# sch.net
KiCad netlist of a schematic drawn in EAGLE
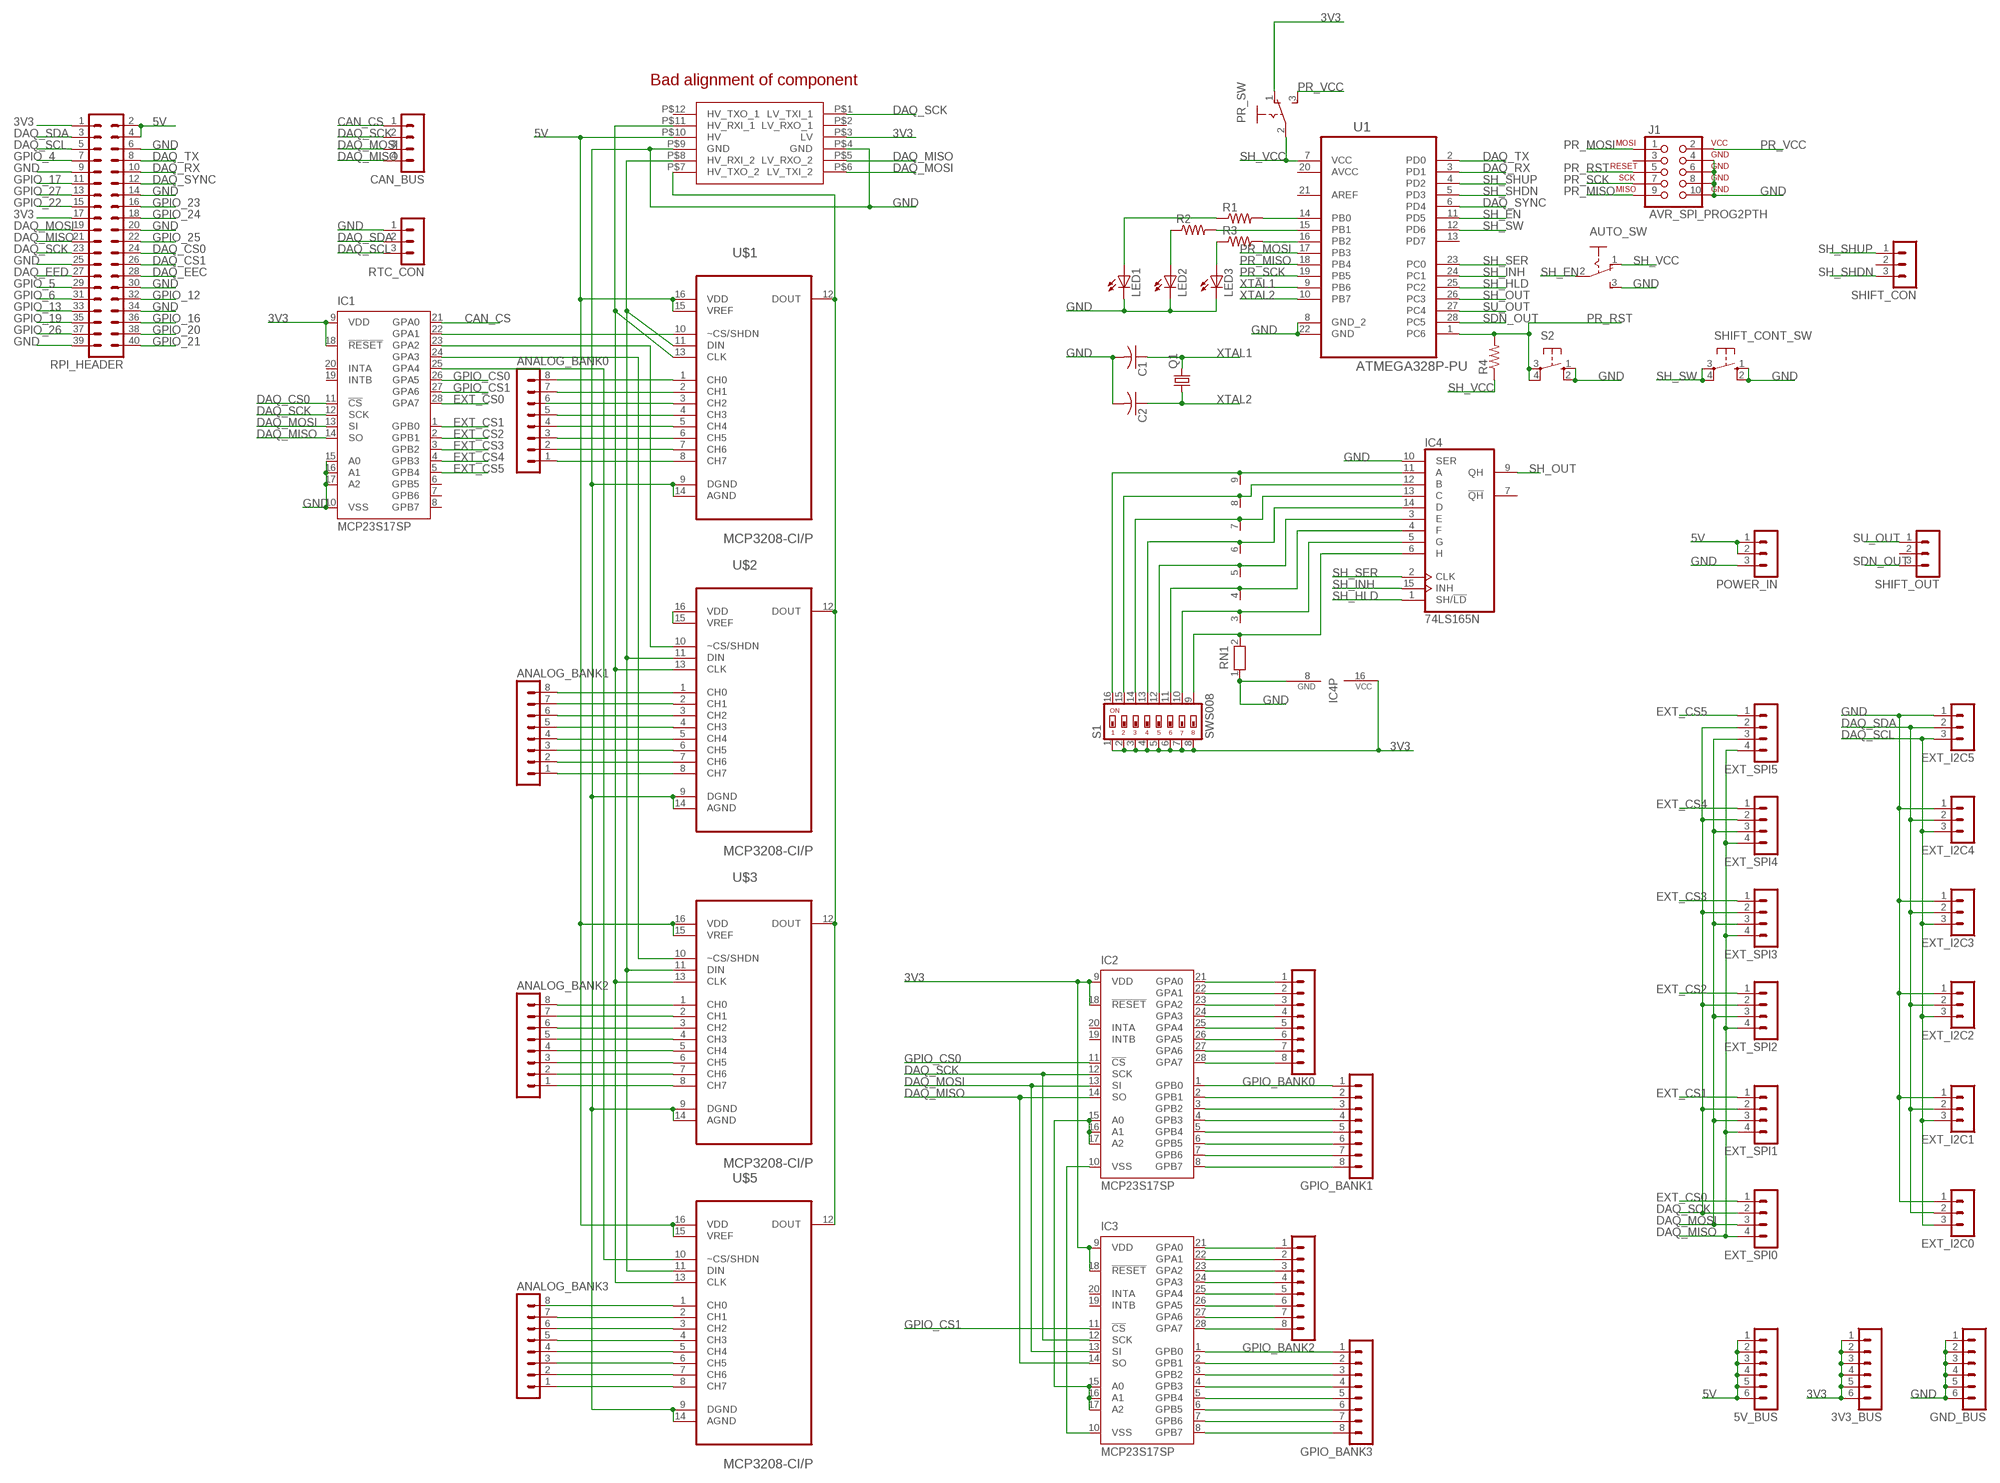
[diagram p0: schematic, sheet 1]

(export (version "E")
  (design (tool "Eeschema 10.0.6"))
  (components
    (comp (ref "3V3_BUS")
      (value "MA06-1")
      (footprint "eagle-import:MA06-1")
      (libsource (lib "eagle-import") (part "MA06-1"))
    )
    (comp (ref "5V_BUS")
      (value "MA06-1")
      (footprint "eagle-import:MA06-1")
      (libsource (lib "eagle-import") (part "MA06-1"))
    )
    (comp (ref "ANALOG_BANK0")
      (value "MA08-1")
      (footprint "eagle-import:MA08-1")
      (libsource (lib "eagle-import") (part "MA08-1"))
    )
    (comp (ref "ANALOG_BANK1")
      (value "MA08-1")
      (footprint "eagle-import:MA08-1")
      (libsource (lib "eagle-import") (part "MA08-1"))
    )
    (comp (ref "ANALOG_BANK2")
      (value "MA08-1")
      (footprint "eagle-import:MA08-1")
      (libsource (lib "eagle-import") (part "MA08-1"))
    )
    (comp (ref "ANALOG_BANK3")
      (value "MA08-1")
      (footprint "eagle-import:MA08-1")
      (libsource (lib "eagle-import") (part "MA08-1"))
    )
    (comp (ref "AUTO_SW")
      (value "255SB")
      (footprint "eagle-import:255SB")
      (libsource (lib "eagle-import") (part "255SB"))
    )
    (comp (ref "C1")
      (value "C-US025-025X050")
      (footprint "eagle-import:C025-025X050")
      (libsource (lib "eagle-import") (part "C-US025-025X050"))
    )
    (comp (ref "C2")
      (value "C-US025-025X050")
      (footprint "eagle-import:C025-025X050")
      (libsource (lib "eagle-import") (part "C-US025-025X050"))
    )
    (comp (ref "CAN_BUS")
      (value "MA04-1")
      (footprint "eagle-import:MA04-1")
      (libsource (lib "eagle-import") (part "MA04-1"))
    )
    (comp (ref "EXT_I2C0")
      (value "MA03-1")
      (footprint "eagle-import:MA03-1")
      (libsource (lib "eagle-import") (part "MA03-1"))
    )
    (comp (ref "EXT_I2C1")
      (value "MA03-1")
      (footprint "eagle-import:MA03-1")
      (libsource (lib "eagle-import") (part "MA03-1"))
    )
    (comp (ref "EXT_I2C2")
      (value "MA03-1")
      (footprint "eagle-import:MA03-1")
      (libsource (lib "eagle-import") (part "MA03-1"))
    )
    (comp (ref "EXT_I2C3")
      (value "MA03-1")
      (footprint "eagle-import:MA03-1")
      (libsource (lib "eagle-import") (part "MA03-1"))
    )
    (comp (ref "EXT_I2C4")
      (value "MA03-1")
      (footprint "eagle-import:MA03-1")
      (libsource (lib "eagle-import") (part "MA03-1"))
    )
    (comp (ref "EXT_I2C5")
      (value "MA03-1")
      (footprint "eagle-import:MA03-1")
      (libsource (lib "eagle-import") (part "MA03-1"))
    )
    (comp (ref "EXT_SPI0")
      (value "MA04-1")
      (footprint "eagle-import:MA04-1")
      (libsource (lib "eagle-import") (part "MA04-1"))
    )
    (comp (ref "EXT_SPI1")
      (value "MA04-1")
      (footprint "eagle-import:MA04-1")
      (libsource (lib "eagle-import") (part "MA04-1"))
    )
    (comp (ref "EXT_SPI2")
      (value "MA04-1")
      (footprint "eagle-import:MA04-1")
      (libsource (lib "eagle-import") (part "MA04-1"))
    )
    (comp (ref "EXT_SPI3")
      (value "MA04-1")
      (footprint "eagle-import:MA04-1")
      (libsource (lib "eagle-import") (part "MA04-1"))
    )
    (comp (ref "EXT_SPI4")
      (value "MA04-1")
      (footprint "eagle-import:MA04-1")
      (libsource (lib "eagle-import") (part "MA04-1"))
    )
    (comp (ref "EXT_SPI5")
      (value "MA04-1")
      (footprint "eagle-import:MA04-1")
      (libsource (lib "eagle-import") (part "MA04-1"))
    )
    (comp (ref "GND_BUS")
      (value "MA06-1")
      (footprint "eagle-import:MA06-1")
      (libsource (lib "eagle-import") (part "MA06-1"))
    )
    (comp (ref "GPIO_BANK0")
      (value "MA08-1")
      (footprint "eagle-import:MA08-1")
      (libsource (lib "eagle-import") (part "MA08-1"))
    )
    (comp (ref "GPIO_BANK1")
      (value "MA08-1")
      (footprint "eagle-import:MA08-1")
      (libsource (lib "eagle-import") (part "MA08-1"))
    )
    (comp (ref "GPIO_BANK2")
      (value "MA08-1")
      (footprint "eagle-import:MA08-1")
      (libsource (lib "eagle-import") (part "MA08-1"))
    )
    (comp (ref "GPIO_BANK3")
      (value "MA08-1")
      (footprint "eagle-import:MA08-1")
      (libsource (lib "eagle-import") (part "MA08-1"))
    )
    (comp (ref "IC1")
      (value "MCP23S17SP")
      (footprint "eagle-import:DIL28-3")
      (fields (field (name "MF") "MICROCHIP") (field (name "MPN") "MCP23S17-E/SP"))
      (libsource (lib "eagle-import") (part "MCP23S17SP"))
    )
    (comp (ref "IC2")
      (value "MCP23S17SP")
      (footprint "eagle-import:DIL28-3")
      (fields (field (name "MF") "MICROCHIP") (field (name "MPN") "MCP23S17-E/SP"))
      (libsource (lib "eagle-import") (part "MCP23S17SP"))
    )
    (comp (ref "IC3")
      (value "MCP23S17SP")
      (footprint "eagle-import:DIL28-3")
      (fields (field (name "MF") "MICROCHIP") (field (name "MPN") "MCP23S17-E/SP"))
      (libsource (lib "eagle-import") (part "MCP23S17SP"))
    )
    (comp (ref "IC4")
      (value "74LS165N")
      (footprint "eagle-import:DIL16")
      (libsource (lib "eagle-import") (part "74165NLS"))
    )
    (comp (ref "J1")
      (value "AVR_SPI_PROG2PTH")
      (footprint "eagle-import:AVR_ICSP")
      (libsource (lib "eagle-import") (part "AVR_SPI_PROG2PTH"))
    )
    (comp (ref "LED1")
      (value "LED3MM")
      (footprint "eagle-import:LED3MM")
      (libsource (lib "eagle-import") (part "LED3MM"))
    )
    (comp (ref "LED2")
      (value "LED3MM")
      (footprint "eagle-import:LED3MM")
      (libsource (lib "eagle-import") (part "LED3MM"))
    )
    (comp (ref "LED3")
      (value "LED3MM")
      (footprint "eagle-import:LED3MM")
      (libsource (lib "eagle-import") (part "LED3MM"))
    )
    (comp (ref "POWER_IN")
      (value "MA03-1")
      (footprint "eagle-import:MA03-1")
      (libsource (lib "eagle-import") (part "MA03-1"))
    )
    (comp (ref "PR_SW")
      (value "255SB")
      (footprint "eagle-import:255SB")
      (libsource (lib "eagle-import") (part "255SB"))
    )
    (comp (ref "Q1")
      (value "CRYSTALHC49S")
      (footprint "eagle-import:HC49_S")
      (libsource (lib "eagle-import") (part "CRYSTALHC49S"))
    )
    (comp (ref "R1")
      (value "R-US_0204/5")
      (footprint "eagle-import:0204_5")
      (libsource (lib "eagle-import") (part "R-US_0204/5"))
    )
    (comp (ref "R2")
      (value "R-US_0204/5")
      (footprint "eagle-import:0204_5")
      (libsource (lib "eagle-import") (part "R-US_0204/5"))
    )
    (comp (ref "R3")
      (value "R-US_0204/5")
      (footprint "eagle-import:0204_5")
      (libsource (lib "eagle-import") (part "R-US_0204/5"))
    )
    (comp (ref "R4")
      (value "R-US_0204/5")
      (footprint "eagle-import:0204_5")
      (libsource (lib "eagle-import") (part "R-US_0204/5"))
    )
    (comp (ref "RN1")
      (value "RN08")
      (footprint "eagle-import:RN-9")
      (libsource (lib "eagle-import") (part "RN08"))
    )
    (comp (ref "RPI_HEADER")
      (value "MA20-2")
      (footprint "eagle-import:MA20-2")
      (libsource (lib "eagle-import") (part "MA20-2"))
    )
    (comp (ref "RTC_CON")
      (value "MA03-1")
      (footprint "eagle-import:MA03-1")
      (libsource (lib "eagle-import") (part "MA03-1"))
    )
    (comp (ref "S1")
      (value "SWS008")
      (footprint "eagle-import:SMS-008")
      (libsource (lib "eagle-import") (part "SWS008"))
    )
    (comp (ref "S2")
      (value "10-XX")
      (footprint "eagle-import:B3F-10XX")
      (fields (field (name "MPN") "B3F-1000"))
      (libsource (lib "eagle-import") (part "10-XX"))
    )
    (comp (ref "SHIFT_CON")
      (value "MA03-1")
      (footprint "eagle-import:MA03-1")
      (libsource (lib "eagle-import") (part "MA03-1"))
    )
    (comp (ref "SHIFT_CONT_SW")
      (value "10-XX")
      (footprint "eagle-import:B3F-10XX")
      (fields (field (name "MPN") "B3F-1000"))
      (libsource (lib "eagle-import") (part "10-XX"))
    )
    (comp (ref "SHIFT_OUT")
      (value "MA03-1")
      (footprint "eagle-import:MA03-1")
      (libsource (lib "eagle-import") (part "MA03-1"))
    )
    (comp (ref "U$1")
      (value "MCP3208-CI/P")
      (footprint "eagle-import:DIP254P762X432-16")
      (libsource (lib "eagle-import") (part "MCP3208-CI/P"))
    )
    (comp (ref "U$2")
      (value "MCP3208-CI/P")
      (footprint "eagle-import:DIP254P762X432-16")
      (libsource (lib "eagle-import") (part "MCP3208-CI/P"))
    )
    (comp (ref "U$3")
      (value "MCP3208-CI/P")
      (footprint "eagle-import:DIP254P762X432-16")
      (libsource (lib "eagle-import") (part "MCP3208-CI/P"))
    )
    (comp (ref "U$4")
      (value "LOGIC_LEVEL_CONVERTER")
      (footprint "eagle-import:LOGIC_LEVEL_CONVERTER")
      (libsource (lib "eagle-import") (part "LOGIC_LEVEL_CONVERTER"))
    )
    (comp (ref "U$5")
      (value "MCP3208-CI/P")
      (footprint "eagle-import:DIP254P762X432-16")
      (libsource (lib "eagle-import") (part "MCP3208-CI/P"))
    )
    (comp (ref "U1")
      (value "ATMEGA328P-PU")
      (footprint "eagle-import:DIP254P762X457-28")
      (libsource (lib "eagle-import") (part "ATMEGA328P-PU"))
    )
  )
  (nets
    (net (code "1") (name "/3V3") (class "Default")
      (node (ref "3V3_BUS") (pin "1") (pinfunction "1_1") (pintype "passive"))
      (node (ref "3V3_BUS") (pin "2") (pinfunction "2_2") (pintype "passive"))
      (node (ref "3V3_BUS") (pin "3") (pinfunction "3_3") (pintype "passive"))
      (node (ref "3V3_BUS") (pin "4") (pinfunction "4_4") (pintype "passive"))
      (node (ref "3V3_BUS") (pin "5") (pinfunction "5_5") (pintype "passive"))
      (node (ref "3V3_BUS") (pin "6") (pinfunction "6_6") (pintype "passive"))
      (node (ref "IC1") (pin "18") (pinfunction "~{RESET}_18") (pintype "input"))
      (node (ref "IC1") (pin "9") (pinfunction "VDD_9") (pintype "power_in"))
      (node (ref "IC2") (pin "18") (pinfunction "~{RESET}_18") (pintype "input"))
      (node (ref "IC2") (pin "9") (pinfunction "VDD_9") (pintype "power_in"))
      (node (ref "IC3") (pin "18") (pinfunction "~{RESET}_18") (pintype "input"))
      (node (ref "IC3") (pin "9") (pinfunction "VDD_9") (pintype "power_in"))
      (node (ref "IC4") (pin "16") (pinfunction "VCC_16") (pintype "power_in"))
      (node (ref "PR_SW") (pin "1") (pinfunction "O_1") (pintype "passive"))
      (node (ref "RPI_HEADER") (pin "1") (pinfunction "1_1") (pintype "passive"))
      (node (ref "RPI_HEADER") (pin "17") (pinfunction "17_17") (pintype "passive"))
      (node (ref "S1") (pin "1") (pinfunction "1_1") (pintype "passive"))
      (node (ref "S1") (pin "2") (pinfunction "2_2") (pintype "passive"))
      (node (ref "S1") (pin "3") (pinfunction "3_3") (pintype "passive"))
      (node (ref "S1") (pin "4") (pinfunction "4_4") (pintype "passive"))
      (node (ref "S1") (pin "5") (pinfunction "5_5") (pintype "passive"))
      (node (ref "S1") (pin "6") (pinfunction "6_6") (pintype "passive"))
      (node (ref "S1") (pin "7") (pinfunction "7_7") (pintype "passive"))
      (node (ref "S1") (pin "8") (pinfunction "8_8") (pintype "passive"))
      (node (ref "U$4") (pin "P$3") (pinfunction "LV_P$3") (pintype "bidirectional"))
    )
    (net (code "2") (name "/5V") (class "Default")
      (node (ref "5V_BUS") (pin "1") (pinfunction "1_1") (pintype "passive"))
      (node (ref "5V_BUS") (pin "2") (pinfunction "2_2") (pintype "passive"))
      (node (ref "5V_BUS") (pin "3") (pinfunction "3_3") (pintype "passive"))
      (node (ref "5V_BUS") (pin "4") (pinfunction "4_4") (pintype "passive"))
      (node (ref "5V_BUS") (pin "5") (pinfunction "5_5") (pintype "passive"))
      (node (ref "5V_BUS") (pin "6") (pinfunction "6_6") (pintype "passive"))
      (node (ref "POWER_IN") (pin "1") (pinfunction "1_1") (pintype "passive"))
      (node (ref "POWER_IN") (pin "2") (pinfunction "2_2") (pintype "passive"))
      (node (ref "RPI_HEADER") (pin "2") (pinfunction "2_2") (pintype "passive"))
      (node (ref "RPI_HEADER") (pin "4") (pinfunction "4_4") (pintype "passive"))
      (node (ref "U$1") (pin "15") (pinfunction "VREF_15") (pintype "power_in"))
      (node (ref "U$1") (pin "16") (pinfunction "VDD_16") (pintype "power_in"))
      (node (ref "U$3") (pin "15") (pinfunction "VREF_15") (pintype "power_in"))
      (node (ref "U$3") (pin "16") (pinfunction "VDD_16") (pintype "power_in"))
      (node (ref "U$4") (pin "P$10") (pinfunction "HV_P$10") (pintype "bidirectional"))
      (node (ref "U$5") (pin "15") (pinfunction "VREF_15") (pintype "power_in"))
      (node (ref "U$5") (pin "16") (pinfunction "VDD_16") (pintype "power_in"))
    )
    (net (code "3") (name "/AVCC") (class "Default")
      (node (ref "U1") (pin "20") (pinfunction "AVCC_20") (pintype "power_in"))
    )
    (net (code "4") (name "/CAN_CS") (class "Default")
      (node (ref "CAN_BUS") (pin "1") (pinfunction "1_1") (pintype "passive"))
      (node (ref "IC1") (pin "21") (pinfunction "GPA0_21") (pintype "bidirectional"))
    )
    (net (code "5") (name "/DAQ_CS0") (class "Default")
      (node (ref "IC1") (pin "11") (pinfunction "~{CS}_11") (pintype "input"))
      (node (ref "RPI_HEADER") (pin "24") (pinfunction "24_24") (pintype "passive"))
    )
    (net (code "6") (name "/DAQ_CS1") (class "Default")
      (node (ref "RPI_HEADER") (pin "26") (pinfunction "26_26") (pintype "passive"))
    )
    (net (code "7") (name "/DAQ_EEC") (class "Default")
      (node (ref "RPI_HEADER") (pin "28") (pinfunction "28_28") (pintype "passive"))
    )
    (net (code "8") (name "/DAQ_EED") (class "Default")
      (node (ref "RPI_HEADER") (pin "27") (pinfunction "27_27") (pintype "passive"))
    )
    (net (code "9") (name "/DAQ_MISO") (class "Default")
      (node (ref "CAN_BUS") (pin "4") (pinfunction "4_4") (pintype "passive"))
      (node (ref "EXT_SPI0") (pin "4") (pinfunction "4_4") (pintype "passive"))
      (node (ref "EXT_SPI1") (pin "4") (pinfunction "4_4") (pintype "passive"))
      (node (ref "EXT_SPI2") (pin "4") (pinfunction "4_4") (pintype "passive"))
      (node (ref "EXT_SPI3") (pin "4") (pinfunction "4_4") (pintype "passive"))
      (node (ref "EXT_SPI4") (pin "4") (pinfunction "4_4") (pintype "passive"))
      (node (ref "EXT_SPI5") (pin "4") (pinfunction "4_4") (pintype "passive"))
      (node (ref "IC1") (pin "14") (pinfunction "SO_14") (pintype "output"))
      (node (ref "IC2") (pin "14") (pinfunction "SO_14") (pintype "output"))
      (node (ref "IC3") (pin "14") (pinfunction "SO_14") (pintype "output"))
      (node (ref "RPI_HEADER") (pin "21") (pinfunction "21_21") (pintype "passive"))
      (node (ref "U$4") (pin "P$5") (pinfunction "LV_RXO_2_P$5") (pintype "bidirectional"))
    )
    (net (code "10") (name "/DAQ_MOSI") (class "Default")
      (node (ref "CAN_BUS") (pin "3") (pinfunction "3_3") (pintype "passive"))
      (node (ref "EXT_SPI0") (pin "3") (pinfunction "3_3") (pintype "passive"))
      (node (ref "EXT_SPI1") (pin "3") (pinfunction "3_3") (pintype "passive"))
      (node (ref "EXT_SPI2") (pin "3") (pinfunction "3_3") (pintype "passive"))
      (node (ref "EXT_SPI3") (pin "3") (pinfunction "3_3") (pintype "passive"))
      (node (ref "EXT_SPI4") (pin "3") (pinfunction "3_3") (pintype "passive"))
      (node (ref "EXT_SPI5") (pin "3") (pinfunction "3_3") (pintype "passive"))
      (node (ref "IC1") (pin "13") (pinfunction "SI_13") (pintype "input"))
      (node (ref "IC2") (pin "13") (pinfunction "SI_13") (pintype "input"))
      (node (ref "IC3") (pin "13") (pinfunction "SI_13") (pintype "input"))
      (node (ref "RPI_HEADER") (pin "19") (pinfunction "19_19") (pintype "passive"))
      (node (ref "U$4") (pin "P$6") (pinfunction "LV_TXI_2_P$6") (pintype "bidirectional"))
    )
    (net (code "11") (name "/DAQ_RX") (class "Default")
      (node (ref "RPI_HEADER") (pin "10") (pinfunction "10_10") (pintype "passive"))
      (node (ref "U1") (pin "3") (pinfunction "PD1_3") (pintype "bidirectional"))
    )
    (net (code "12") (name "/DAQ_SCK") (class "Default")
      (node (ref "CAN_BUS") (pin "2") (pinfunction "2_2") (pintype "passive"))
      (node (ref "EXT_SPI0") (pin "2") (pinfunction "2_2") (pintype "passive"))
      (node (ref "EXT_SPI1") (pin "2") (pinfunction "2_2") (pintype "passive"))
      (node (ref "EXT_SPI2") (pin "2") (pinfunction "2_2") (pintype "passive"))
      (node (ref "EXT_SPI3") (pin "2") (pinfunction "2_2") (pintype "passive"))
      (node (ref "EXT_SPI4") (pin "2") (pinfunction "2_2") (pintype "passive"))
      (node (ref "EXT_SPI5") (pin "2") (pinfunction "2_2") (pintype "passive"))
      (node (ref "IC1") (pin "12") (pinfunction "SCK_12") (pintype "input"))
      (node (ref "IC2") (pin "12") (pinfunction "SCK_12") (pintype "input"))
      (node (ref "IC3") (pin "12") (pinfunction "SCK_12") (pintype "input"))
      (node (ref "RPI_HEADER") (pin "23") (pinfunction "23_23") (pintype "passive"))
      (node (ref "U$4") (pin "P$1") (pinfunction "LV_TXI_1_P$1") (pintype "bidirectional"))
    )
    (net (code "13") (name "/DAQ_SCL") (class "Default")
      (node (ref "EXT_I2C0") (pin "3") (pinfunction "3_3") (pintype "passive"))
      (node (ref "EXT_I2C1") (pin "3") (pinfunction "3_3") (pintype "passive"))
      (node (ref "EXT_I2C2") (pin "3") (pinfunction "3_3") (pintype "passive"))
      (node (ref "EXT_I2C3") (pin "3") (pinfunction "3_3") (pintype "passive"))
      (node (ref "EXT_I2C4") (pin "3") (pinfunction "3_3") (pintype "passive"))
      (node (ref "EXT_I2C5") (pin "3") (pinfunction "3_3") (pintype "passive"))
      (node (ref "RPI_HEADER") (pin "5") (pinfunction "5_5") (pintype "passive"))
      (node (ref "RTC_CON") (pin "3") (pinfunction "3_3") (pintype "passive"))
    )
    (net (code "14") (name "/DAQ_SDA") (class "Default")
      (node (ref "EXT_I2C0") (pin "2") (pinfunction "2_2") (pintype "passive"))
      (node (ref "EXT_I2C1") (pin "2") (pinfunction "2_2") (pintype "passive"))
      (node (ref "EXT_I2C2") (pin "2") (pinfunction "2_2") (pintype "passive"))
      (node (ref "EXT_I2C3") (pin "2") (pinfunction "2_2") (pintype "passive"))
      (node (ref "EXT_I2C4") (pin "2") (pinfunction "2_2") (pintype "passive"))
      (node (ref "EXT_I2C5") (pin "2") (pinfunction "2_2") (pintype "passive"))
      (node (ref "RPI_HEADER") (pin "3") (pinfunction "3_3") (pintype "passive"))
      (node (ref "RTC_CON") (pin "2") (pinfunction "2_2") (pintype "passive"))
    )
    (net (code "15") (name "/DAQ_SYNC") (class "Default")
      (node (ref "RPI_HEADER") (pin "12") (pinfunction "12_12") (pintype "passive"))
      (node (ref "U1") (pin "6") (pinfunction "PD4_6") (pintype "bidirectional"))
    )
    (net (code "16") (name "/DAQ_TX") (class "Default")
      (node (ref "RPI_HEADER") (pin "8") (pinfunction "8_8") (pintype "passive"))
      (node (ref "U1") (pin "2") (pinfunction "PD0_2") (pintype "bidirectional"))
    )
    (net (code "17") (name "/EXT_CS0") (class "Default")
      (node (ref "EXT_SPI0") (pin "1") (pinfunction "1_1") (pintype "passive"))
      (node (ref "IC1") (pin "28") (pinfunction "GPA7_28") (pintype "bidirectional"))
    )
    (net (code "18") (name "/EXT_CS1") (class "Default")
      (node (ref "EXT_SPI1") (pin "1") (pinfunction "1_1") (pintype "passive"))
      (node (ref "IC1") (pin "1") (pinfunction "GPB0_1") (pintype "bidirectional"))
    )
    (net (code "19") (name "/EXT_CS2") (class "Default")
      (node (ref "EXT_SPI2") (pin "1") (pinfunction "1_1") (pintype "passive"))
      (node (ref "IC1") (pin "2") (pinfunction "GPB1_2") (pintype "bidirectional"))
    )
    (net (code "20") (name "/EXT_CS3") (class "Default")
      (node (ref "EXT_SPI3") (pin "1") (pinfunction "1_1") (pintype "passive"))
      (node (ref "IC1") (pin "3") (pinfunction "GPB2_3") (pintype "bidirectional"))
    )
    (net (code "21") (name "/EXT_CS4") (class "Default")
      (node (ref "EXT_SPI4") (pin "1") (pinfunction "1_1") (pintype "passive"))
      (node (ref "IC1") (pin "4") (pinfunction "GPB3_4") (pintype "bidirectional"))
    )
    (net (code "22") (name "/EXT_CS5") (class "Default")
      (node (ref "EXT_SPI5") (pin "1") (pinfunction "1_1") (pintype "passive"))
      (node (ref "IC1") (pin "5") (pinfunction "GPB4_5") (pintype "bidirectional"))
    )
    (net (code "23") (name "/GND") (class "Default")
      (node (ref "AUTO_SW") (pin "3") (pinfunction "S_3") (pintype "passive"))
      (node (ref "C1") (pin "2") (pinfunction "2_2") (pintype "passive"))
      (node (ref "C2") (pin "2") (pinfunction "2_2") (pintype "passive"))
      (node (ref "EXT_I2C0") (pin "1") (pinfunction "1_1") (pintype "passive"))
      (node (ref "EXT_I2C1") (pin "1") (pinfunction "1_1") (pintype "passive"))
      (node (ref "EXT_I2C2") (pin "1") (pinfunction "1_1") (pintype "passive"))
      (node (ref "EXT_I2C3") (pin "1") (pinfunction "1_1") (pintype "passive"))
      (node (ref "EXT_I2C4") (pin "1") (pinfunction "1_1") (pintype "passive"))
      (node (ref "EXT_I2C5") (pin "1") (pinfunction "1_1") (pintype "passive"))
      (node (ref "GND_BUS") (pin "1") (pinfunction "1_1") (pintype "passive"))
      (node (ref "GND_BUS") (pin "2") (pinfunction "2_2") (pintype "passive"))
      (node (ref "GND_BUS") (pin "3") (pinfunction "3_3") (pintype "passive"))
      (node (ref "GND_BUS") (pin "4") (pinfunction "4_4") (pintype "passive"))
      (node (ref "GND_BUS") (pin "5") (pinfunction "5_5") (pintype "passive"))
      (node (ref "GND_BUS") (pin "6") (pinfunction "6_6") (pintype "passive"))
      (node (ref "IC1") (pin "10") (pinfunction "VSS_10") (pintype "power_in"))
      (node (ref "IC1") (pin "15") (pinfunction "A0_15") (pintype "input"))
      (node (ref "IC1") (pin "16") (pinfunction "A1_16") (pintype "input"))
      (node (ref "IC1") (pin "17") (pinfunction "A2_17") (pintype "input"))
      (node (ref "IC4") (pin "10") (pinfunction "SER_10") (pintype "input"))
      (node (ref "IC4") (pin "8") (pinfunction "GND_8") (pintype "power_in"))
      (node (ref "J1") (pin "10") (pinfunction "GND_10") (pintype "power_in"))
      (node (ref "J1") (pin "4") (pinfunction "GND_4") (pintype "power_in"))
      (node (ref "J1") (pin "6") (pinfunction "GND_6") (pintype "power_in"))
      (node (ref "J1") (pin "8") (pinfunction "GND_8") (pintype "power_in"))
      (node (ref "LED1") (pin "K") (pinfunction "C_K") (pintype "passive"))
      (node (ref "LED2") (pin "K") (pinfunction "C_K") (pintype "passive"))
      (node (ref "LED3") (pin "K") (pinfunction "C_K") (pintype "passive"))
      (node (ref "POWER_IN") (pin "3") (pinfunction "3_3") (pintype "passive"))
      (node (ref "RN1") (pin "1") (pinfunction "1_1") (pintype "passive"))
      (node (ref "RPI_HEADER") (pin "14") (pinfunction "14_14") (pintype "passive"))
      (node (ref "RPI_HEADER") (pin "20") (pinfunction "20_20") (pintype "passive"))
      (node (ref "RPI_HEADER") (pin "25") (pinfunction "25_25") (pintype "passive"))
      (node (ref "RPI_HEADER") (pin "30") (pinfunction "30_30") (pintype "passive"))
      (node (ref "RPI_HEADER") (pin "34") (pinfunction "34_34") (pintype "passive"))
      (node (ref "RPI_HEADER") (pin "39") (pinfunction "39_39") (pintype "passive"))
      (node (ref "RPI_HEADER") (pin "6") (pinfunction "6_6") (pintype "passive"))
      (node (ref "RPI_HEADER") (pin "9") (pinfunction "9_9") (pintype "passive"))
      (node (ref "RTC_CON") (pin "1") (pinfunction "1_1") (pintype "passive"))
      (node (ref "S2") (pin "1") (pinfunction "S_1") (pintype "passive"))
      (node (ref "S2") (pin "2") (pinfunction "S1_2") (pintype "passive"))
      (node (ref "SHIFT_CONT_SW") (pin "1") (pinfunction "S_1") (pintype "passive"))
      (node (ref "SHIFT_CONT_SW") (pin "2") (pinfunction "S1_2") (pintype "passive"))
      (node (ref "U$1") (pin "14") (pinfunction "AGND_14") (pintype "passive"))
      (node (ref "U$1") (pin "9") (pinfunction "DGND_9") (pintype "passive"))
      (node (ref "U$2") (pin "14") (pinfunction "AGND_14") (pintype "passive"))
      (node (ref "U$2") (pin "9") (pinfunction "DGND_9") (pintype "passive"))
      (node (ref "U$3") (pin "14") (pinfunction "AGND_14") (pintype "passive"))
      (node (ref "U$3") (pin "9") (pinfunction "DGND_9") (pintype "passive"))
      (node (ref "U$4") (pin "P$4") (pinfunction "GND_P$4") (pintype "bidirectional"))
      (node (ref "U$4") (pin "P$9") (pinfunction "GND_P$9") (pintype "bidirectional"))
      (node (ref "U$5") (pin "14") (pinfunction "AGND_14") (pintype "passive"))
      (node (ref "U$5") (pin "9") (pinfunction "DGND_9") (pintype "passive"))
      (node (ref "U1") (pin "22") (pinfunction "GND_22") (pintype "passive"))
      (node (ref "U1") (pin "8") (pinfunction "GND_2_8") (pintype "passive"))
    )
    (net (code "24") (name "/GPIO_4") (class "Default")
      (node (ref "RPI_HEADER") (pin "7") (pinfunction "7_7") (pintype "passive"))
    )
    (net (code "25") (name "/GPIO_5") (class "Default")
      (node (ref "RPI_HEADER") (pin "29") (pinfunction "29_29") (pintype "passive"))
    )
    (net (code "26") (name "/GPIO_6") (class "Default")
      (node (ref "RPI_HEADER") (pin "31") (pinfunction "31_31") (pintype "passive"))
    )
    (net (code "27") (name "/GPIO_12") (class "Default")
      (node (ref "RPI_HEADER") (pin "32") (pinfunction "32_32") (pintype "passive"))
    )
    (net (code "28") (name "/GPIO_13") (class "Default")
      (node (ref "RPI_HEADER") (pin "33") (pinfunction "33_33") (pintype "passive"))
    )
    (net (code "29") (name "/GPIO_16") (class "Default")
      (node (ref "RPI_HEADER") (pin "36") (pinfunction "36_36") (pintype "passive"))
    )
    (net (code "30") (name "/GPIO_17") (class "Default")
      (node (ref "RPI_HEADER") (pin "11") (pinfunction "11_11") (pintype "passive"))
    )
    (net (code "31") (name "/GPIO_19") (class "Default")
      (node (ref "RPI_HEADER") (pin "35") (pinfunction "35_35") (pintype "passive"))
    )
    (net (code "32") (name "/GPIO_20") (class "Default")
      (node (ref "RPI_HEADER") (pin "38") (pinfunction "38_38") (pintype "passive"))
    )
    (net (code "33") (name "/GPIO_21") (class "Default")
      (node (ref "RPI_HEADER") (pin "40") (pinfunction "40_40") (pintype "passive"))
    )
    (net (code "34") (name "/GPIO_22") (class "Default")
      (node (ref "RPI_HEADER") (pin "15") (pinfunction "15_15") (pintype "passive"))
    )
    (net (code "35") (name "/GPIO_23") (class "Default")
      (node (ref "RPI_HEADER") (pin "16") (pinfunction "16_16") (pintype "passive"))
    )
    (net (code "36") (name "/GPIO_24") (class "Default")
      (node (ref "RPI_HEADER") (pin "18") (pinfunction "18_18") (pintype "passive"))
    )
    (net (code "37") (name "/GPIO_25") (class "Default")
      (node (ref "RPI_HEADER") (pin "22") (pinfunction "22_22") (pintype "passive"))
    )
    (net (code "38") (name "/GPIO_26") (class "Default")
      (node (ref "RPI_HEADER") (pin "37") (pinfunction "37_37") (pintype "passive"))
    )
    (net (code "39") (name "/GPIO_27") (class "Default")
      (node (ref "RPI_HEADER") (pin "13") (pinfunction "13_13") (pintype "passive"))
    )
    (net (code "40") (name "/GPIO_CS0") (class "Default")
      (node (ref "IC1") (pin "26") (pinfunction "GPA5_26") (pintype "bidirectional"))
      (node (ref "IC2") (pin "11") (pinfunction "~{CS}_11") (pintype "input"))
    )
    (net (code "41") (name "/GPIO_CS1") (class "Default")
      (node (ref "IC1") (pin "27") (pinfunction "GPA6_27") (pintype "bidirectional"))
      (node (ref "IC3") (pin "11") (pinfunction "~{CS}_11") (pintype "input"))
    )
    (net (code "42") (name "/PR_MISO") (class "Default")
      (node (ref "J1") (pin "9") (pinfunction "MISO_9") (pintype "passive"))
      (node (ref "U1") (pin "18") (pinfunction "PB4_18") (pintype "bidirectional"))
    )
    (net (code "43") (name "/PR_MOSI") (class "Default")
      (node (ref "J1") (pin "1") (pinfunction "MOSI_1") (pintype "passive"))
      (node (ref "U1") (pin "17") (pinfunction "PB3_17") (pintype "bidirectional"))
    )
    (net (code "44") (name "/PR_RST") (class "Default")
      (node (ref "J1") (pin "5") (pinfunction "RESET_5") (pintype "passive"))
      (node (ref "R4") (pin "2") (pinfunction "2_2") (pintype "passive"))
      (node (ref "S2") (pin "3") (pinfunction "P_3") (pintype "passive"))
      (node (ref "S2") (pin "4") (pinfunction "P1_4") (pintype "passive"))
      (node (ref "U1") (pin "1") (pinfunction "PC6_1") (pintype "bidirectional"))
    )
    (net (code "45") (name "/PR_SCK") (class "Default")
      (node (ref "J1") (pin "7") (pinfunction "SCK_7") (pintype "passive"))
      (node (ref "U1") (pin "19") (pinfunction "PB5_19") (pintype "bidirectional"))
    )
    (net (code "46") (name "/PR_VCC") (class "Default")
      (node (ref "J1") (pin "2") (pinfunction "VCC_2") (pintype "power_in"))
      (node (ref "PR_SW") (pin "3") (pinfunction "S_3") (pintype "passive"))
    )
    (net (code "47") (name "/SDN_OUT") (class "Default")
      (node (ref "SHIFT_OUT") (pin "3") (pinfunction "3_3") (pintype "passive"))
      (node (ref "U1") (pin "28") (pinfunction "PC5_28") (pintype "bidirectional"))
    )
    (net (code "48") (name "/SH_EN") (class "Default")
      (node (ref "AUTO_SW") (pin "2") (pinfunction "P_2") (pintype "passive"))
      (node (ref "U1") (pin "11") (pinfunction "PD5_11") (pintype "bidirectional"))
    )
    (net (code "49") (name "/SH_HLD") (class "Default")
      (node (ref "IC4") (pin "1") (pinfunction "SH/~{LD}_1") (pintype "input"))
      (node (ref "U1") (pin "25") (pinfunction "PC2_25") (pintype "bidirectional"))
    )
    (net (code "50") (name "/SH_INH") (class "Default")
      (node (ref "IC4") (pin "15") (pinfunction "INH_15") (pintype "input"))
      (node (ref "U1") (pin "24") (pinfunction "PC1_24") (pintype "bidirectional"))
    )
    (net (code "51") (name "/SH_OUT") (class "Default")
      (node (ref "IC4") (pin "9") (pinfunction "QH_9") (pintype "output"))
      (node (ref "U1") (pin "26") (pinfunction "PC3_26") (pintype "bidirectional"))
    )
    (net (code "52") (name "/SH_SER") (class "Default")
      (node (ref "IC4") (pin "2") (pinfunction "CLK_2") (pintype "input"))
      (node (ref "U1") (pin "23") (pinfunction "PC0_23") (pintype "bidirectional"))
    )
    (net (code "53") (name "/SH_SHDN") (class "Default")
      (node (ref "SHIFT_CON") (pin "3") (pinfunction "3_3") (pintype "passive"))
      (node (ref "U1") (pin "5") (pinfunction "PD3_5") (pintype "bidirectional"))
    )
    (net (code "54") (name "/SH_SHUP") (class "Default")
      (node (ref "SHIFT_CON") (pin "1") (pinfunction "1_1") (pintype "passive"))
      (node (ref "U1") (pin "4") (pinfunction "PD2_4") (pintype "bidirectional"))
    )
    (net (code "55") (name "/SH_SW") (class "Default")
      (node (ref "SHIFT_CONT_SW") (pin "3") (pinfunction "P_3") (pintype "passive"))
      (node (ref "SHIFT_CONT_SW") (pin "4") (pinfunction "P1_4") (pintype "passive"))
      (node (ref "U1") (pin "12") (pinfunction "PD6_12") (pintype "bidirectional"))
    )
    (net (code "56") (name "/SH_VCC") (class "Default")
      (node (ref "AUTO_SW") (pin "1") (pinfunction "O_1") (pintype "passive"))
      (node (ref "PR_SW") (pin "2") (pinfunction "P_2") (pintype "passive"))
      (node (ref "R4") (pin "1") (pinfunction "1_1") (pintype "passive"))
      (node (ref "U1") (pin "7") (pinfunction "VCC_7") (pintype "power_in"))
    )
    (net (code "57") (name "/SU_OUT") (class "Default")
      (node (ref "SHIFT_OUT") (pin "1") (pinfunction "1_1") (pintype "passive"))
      (node (ref "U1") (pin "27") (pinfunction "PC4_27") (pintype "bidirectional"))
    )
    (net (code "58") (name "/XTAL1") (class "Default")
      (node (ref "C1") (pin "1") (pinfunction "1_1") (pintype "passive"))
      (node (ref "Q1") (pin "2") (pinfunction "2_2") (pintype "passive"))
      (node (ref "U1") (pin "9") (pinfunction "PB6_9") (pintype "bidirectional"))
    )
    (net (code "59") (name "/XTAL2") (class "Default")
      (node (ref "C2") (pin "1") (pinfunction "1_1") (pintype "passive"))
      (node (ref "Q1") (pin "1") (pinfunction "1_1") (pintype "passive"))
      (node (ref "U1") (pin "10") (pinfunction "PB7_10") (pintype "bidirectional"))
    )
    (net (code "60") (name "Net-(IC1-GPA1)") (class "Default")
      (node (ref "IC1") (pin "22") (pinfunction "GPA1_22") (pintype "bidirectional"))
      (node (ref "U$1") (pin "10") (pinfunction "~{CS/SHDN}_10") (pintype "input"))
    )
    (net (code "61") (name "Net-(IC1-GPA2)") (class "Default")
      (node (ref "IC1") (pin "23") (pinfunction "GPA2_23") (pintype "bidirectional"))
      (node (ref "U$2") (pin "10") (pinfunction "~{CS/SHDN}_10") (pintype "input"))
    )
    (net (code "62") (name "Net-(IC1-GPA3)") (class "Default")
      (node (ref "IC1") (pin "24") (pinfunction "GPA3_24") (pintype "bidirectional"))
      (node (ref "U$3") (pin "10") (pinfunction "~{CS/SHDN}_10") (pintype "input"))
    )
    (net (code "63") (name "Net-(IC1-GPA4)") (class "Default")
      (node (ref "IC1") (pin "25") (pinfunction "GPA4_25") (pintype "bidirectional"))
      (node (ref "U$5") (pin "10") (pinfunction "~{CS/SHDN}_10") (pintype "input"))
    )
    (net (code "64") (name "Net-(IC2-A0)") (class "Default")
      (node (ref "IC2") (pin "15") (pinfunction "A0_15") (pintype "input"))
      (node (ref "IC2") (pin "16") (pinfunction "A1_16") (pintype "input"))
      (node (ref "IC2") (pin "17") (pinfunction "A2_17") (pintype "input"))
      (node (ref "IC3") (pin "15") (pinfunction "A0_15") (pintype "input"))
      (node (ref "IC3") (pin "16") (pinfunction "A1_16") (pintype "input"))
      (node (ref "IC3") (pin "17") (pinfunction "A2_17") (pintype "input"))
    )
    (net (code "65") (name "Net-(IC2-GPA0)") (class "Default")
      (node (ref "GPIO_BANK0") (pin "1") (pinfunction "1_1") (pintype "passive"))
      (node (ref "IC2") (pin "21") (pinfunction "GPA0_21") (pintype "bidirectional"))
    )
    (net (code "66") (name "Net-(IC2-GPA1)") (class "Default")
      (node (ref "GPIO_BANK0") (pin "2") (pinfunction "2_2") (pintype "passive"))
      (node (ref "IC2") (pin "22") (pinfunction "GPA1_22") (pintype "bidirectional"))
    )
    (net (code "67") (name "Net-(IC2-GPA2)") (class "Default")
      (node (ref "GPIO_BANK0") (pin "3") (pinfunction "3_3") (pintype "passive"))
      (node (ref "IC2") (pin "23") (pinfunction "GPA2_23") (pintype "bidirectional"))
    )
    (net (code "68") (name "Net-(IC2-GPA3)") (class "Default")
      (node (ref "GPIO_BANK0") (pin "4") (pinfunction "4_4") (pintype "passive"))
      (node (ref "IC2") (pin "24") (pinfunction "GPA3_24") (pintype "bidirectional"))
    )
    (net (code "69") (name "Net-(IC2-GPA4)") (class "Default")
      (node (ref "GPIO_BANK0") (pin "5") (pinfunction "5_5") (pintype "passive"))
      (node (ref "IC2") (pin "25") (pinfunction "GPA4_25") (pintype "bidirectional"))
    )
    (net (code "70") (name "Net-(IC2-GPA5)") (class "Default")
      (node (ref "GPIO_BANK0") (pin "6") (pinfunction "6_6") (pintype "passive"))
      (node (ref "IC2") (pin "26") (pinfunction "GPA5_26") (pintype "bidirectional"))
    )
    (net (code "71") (name "Net-(IC2-GPA6)") (class "Default")
      (node (ref "GPIO_BANK0") (pin "7") (pinfunction "7_7") (pintype "passive"))
      (node (ref "IC2") (pin "27") (pinfunction "GPA6_27") (pintype "bidirectional"))
    )
    (net (code "72") (name "Net-(IC2-GPA7)") (class "Default")
      (node (ref "GPIO_BANK0") (pin "8") (pinfunction "8_8") (pintype "passive"))
      (node (ref "IC2") (pin "28") (pinfunction "GPA7_28") (pintype "bidirectional"))
    )
    (net (code "73") (name "Net-(IC2-GPB0)") (class "Default")
      (node (ref "GPIO_BANK1") (pin "1") (pinfunction "1_1") (pintype "passive"))
      (node (ref "IC2") (pin "1") (pinfunction "GPB0_1") (pintype "bidirectional"))
    )
    (net (code "74") (name "Net-(IC2-GPB1)") (class "Default")
      (node (ref "GPIO_BANK1") (pin "2") (pinfunction "2_2") (pintype "passive"))
      (node (ref "IC2") (pin "2") (pinfunction "GPB1_2") (pintype "bidirectional"))
    )
    (net (code "75") (name "Net-(IC2-GPB2)") (class "Default")
      (node (ref "GPIO_BANK1") (pin "3") (pinfunction "3_3") (pintype "passive"))
      (node (ref "IC2") (pin "3") (pinfunction "GPB2_3") (pintype "bidirectional"))
    )
    (net (code "76") (name "Net-(IC2-GPB3)") (class "Default")
      (node (ref "GPIO_BANK1") (pin "4") (pinfunction "4_4") (pintype "passive"))
      (node (ref "IC2") (pin "4") (pinfunction "GPB3_4") (pintype "bidirectional"))
    )
    (net (code "77") (name "Net-(IC2-GPB4)") (class "Default")
      (node (ref "GPIO_BANK1") (pin "5") (pinfunction "5_5") (pintype "passive"))
      (node (ref "IC2") (pin "5") (pinfunction "GPB4_5") (pintype "bidirectional"))
    )
    (net (code "78") (name "Net-(IC2-GPB5)") (class "Default")
      (node (ref "GPIO_BANK1") (pin "6") (pinfunction "6_6") (pintype "passive"))
      (node (ref "IC2") (pin "6") (pinfunction "GPB5_6") (pintype "bidirectional"))
    )
    (net (code "79") (name "Net-(IC2-GPB6)") (class "Default")
      (node (ref "GPIO_BANK1") (pin "7") (pinfunction "7_7") (pintype "passive"))
      (node (ref "IC2") (pin "7") (pinfunction "GPB6_7") (pintype "bidirectional"))
    )
    (net (code "80") (name "Net-(IC2-GPB7)") (class "Default")
      (node (ref "GPIO_BANK1") (pin "8") (pinfunction "8_8") (pintype "passive"))
      (node (ref "IC2") (pin "8") (pinfunction "GPB7_8") (pintype "bidirectional"))
    )
    (net (code "81") (name "Net-(IC2-VSS)") (class "Default")
      (node (ref "IC2") (pin "10") (pinfunction "VSS_10") (pintype "power_in"))
      (node (ref "IC3") (pin "10") (pinfunction "VSS_10") (pintype "power_in"))
    )
    (net (code "82") (name "Net-(IC3-GPA0)") (class "Default")
      (node (ref "GPIO_BANK2") (pin "1") (pinfunction "1_1") (pintype "passive"))
      (node (ref "IC3") (pin "21") (pinfunction "GPA0_21") (pintype "bidirectional"))
    )
    (net (code "83") (name "Net-(IC3-GPA1)") (class "Default")
      (node (ref "GPIO_BANK2") (pin "2") (pinfunction "2_2") (pintype "passive"))
      (node (ref "IC3") (pin "22") (pinfunction "GPA1_22") (pintype "bidirectional"))
    )
    (net (code "84") (name "Net-(IC3-GPA2)") (class "Default")
      (node (ref "GPIO_BANK2") (pin "3") (pinfunction "3_3") (pintype "passive"))
      (node (ref "IC3") (pin "23") (pinfunction "GPA2_23") (pintype "bidirectional"))
    )
    (net (code "85") (name "Net-(IC3-GPA3)") (class "Default")
      (node (ref "GPIO_BANK2") (pin "4") (pinfunction "4_4") (pintype "passive"))
      (node (ref "IC3") (pin "24") (pinfunction "GPA3_24") (pintype "bidirectional"))
    )
    (net (code "86") (name "Net-(IC3-GPA4)") (class "Default")
      (node (ref "GPIO_BANK2") (pin "5") (pinfunction "5_5") (pintype "passive"))
      (node (ref "IC3") (pin "25") (pinfunction "GPA4_25") (pintype "bidirectional"))
    )
    (net (code "87") (name "Net-(IC3-GPA5)") (class "Default")
      (node (ref "GPIO_BANK2") (pin "6") (pinfunction "6_6") (pintype "passive"))
      (node (ref "IC3") (pin "26") (pinfunction "GPA5_26") (pintype "bidirectional"))
    )
    (net (code "88") (name "Net-(IC3-GPA6)") (class "Default")
      (node (ref "GPIO_BANK2") (pin "7") (pinfunction "7_7") (pintype "passive"))
      (node (ref "IC3") (pin "27") (pinfunction "GPA6_27") (pintype "bidirectional"))
    )
    (net (code "89") (name "Net-(IC3-GPA7)") (class "Default")
      (node (ref "GPIO_BANK2") (pin "8") (pinfunction "8_8") (pintype "passive"))
      (node (ref "IC3") (pin "28") (pinfunction "GPA7_28") (pintype "bidirectional"))
    )
    (net (code "90") (name "Net-(IC3-GPB0)") (class "Default")
      (node (ref "GPIO_BANK3") (pin "1") (pinfunction "1_1") (pintype "passive"))
      (node (ref "IC3") (pin "1") (pinfunction "GPB0_1") (pintype "bidirectional"))
    )
    (net (code "91") (name "Net-(IC3-GPB1)") (class "Default")
      (node (ref "GPIO_BANK3") (pin "2") (pinfunction "2_2") (pintype "passive"))
      (node (ref "IC3") (pin "2") (pinfunction "GPB1_2") (pintype "bidirectional"))
    )
    (net (code "92") (name "Net-(IC3-GPB2)") (class "Default")
      (node (ref "GPIO_BANK3") (pin "3") (pinfunction "3_3") (pintype "passive"))
      (node (ref "IC3") (pin "3") (pinfunction "GPB2_3") (pintype "bidirectional"))
    )
    (net (code "93") (name "Net-(IC3-GPB3)") (class "Default")
      (node (ref "GPIO_BANK3") (pin "4") (pinfunction "4_4") (pintype "passive"))
      (node (ref "IC3") (pin "4") (pinfunction "GPB3_4") (pintype "bidirectional"))
    )
    (net (code "94") (name "Net-(IC3-GPB4)") (class "Default")
      (node (ref "GPIO_BANK3") (pin "5") (pinfunction "5_5") (pintype "passive"))
      (node (ref "IC3") (pin "5") (pinfunction "GPB4_5") (pintype "bidirectional"))
    )
    (net (code "95") (name "Net-(IC3-GPB5)") (class "Default")
      (node (ref "GPIO_BANK3") (pin "6") (pinfunction "6_6") (pintype "passive"))
      (node (ref "IC3") (pin "6") (pinfunction "GPB5_6") (pintype "bidirectional"))
    )
    (net (code "96") (name "Net-(IC3-GPB6)") (class "Default")
      (node (ref "GPIO_BANK3") (pin "7") (pinfunction "7_7") (pintype "passive"))
      (node (ref "IC3") (pin "7") (pinfunction "GPB6_7") (pintype "bidirectional"))
    )
    (net (code "97") (name "Net-(IC3-GPB7)") (class "Default")
      (node (ref "GPIO_BANK3") (pin "8") (pinfunction "8_8") (pintype "passive"))
      (node (ref "IC3") (pin "8") (pinfunction "GPB7_8") (pintype "bidirectional"))
    )
    (net (code "98") (name "Net-(IC4A-A)") (class "Default")
      (node (ref "IC4") (pin "11") (pinfunction "A_11") (pintype "input"))
      (node (ref "RN1") (pin "9") (pinfunction "9_9") (pintype "passive"))
      (node (ref "S1") (pin "16") (pinfunction "16_16") (pintype "passive"))
    )
    (net (code "99") (name "Net-(IC4A-B)") (class "Default")
      (node (ref "IC4") (pin "12") (pinfunction "B_12") (pintype "input"))
      (node (ref "RN1") (pin "8") (pinfunction "8_8") (pintype "passive"))
      (node (ref "S1") (pin "15") (pinfunction "15_15") (pintype "passive"))
    )
    (net (code "100") (name "Net-(IC4A-C)") (class "Default")
      (node (ref "IC4") (pin "13") (pinfunction "C_13") (pintype "input"))
      (node (ref "RN1") (pin "7") (pinfunction "7_7") (pintype "passive"))
      (node (ref "S1") (pin "14") (pinfunction "14_14") (pintype "passive"))
    )
    (net (code "101") (name "Net-(IC4A-D)") (class "Default")
      (node (ref "IC4") (pin "14") (pinfunction "D_14") (pintype "input"))
      (node (ref "RN1") (pin "6") (pinfunction "6_6") (pintype "passive"))
      (node (ref "S1") (pin "13") (pinfunction "13_13") (pintype "passive"))
    )
    (net (code "102") (name "Net-(IC4A-E)") (class "Default")
      (node (ref "IC4") (pin "3") (pinfunction "E_3") (pintype "input"))
      (node (ref "RN1") (pin "5") (pinfunction "5_5") (pintype "passive"))
      (node (ref "S1") (pin "12") (pinfunction "12_12") (pintype "passive"))
    )
    (net (code "103") (name "Net-(IC4A-F)") (class "Default")
      (node (ref "IC4") (pin "4") (pinfunction "F_4") (pintype "input"))
      (node (ref "RN1") (pin "4") (pinfunction "4_4") (pintype "passive"))
      (node (ref "S1") (pin "11") (pinfunction "11_11") (pintype "passive"))
    )
    (net (code "104") (name "Net-(IC4A-G)") (class "Default")
      (node (ref "IC4") (pin "5") (pinfunction "G_5") (pintype "input"))
      (node (ref "RN1") (pin "3") (pinfunction "3_3") (pintype "passive"))
      (node (ref "S1") (pin "10") (pinfunction "10_10") (pintype "passive"))
    )
    (net (code "105") (name "Net-(IC4A-H)") (class "Default")
      (node (ref "IC4") (pin "6") (pinfunction "H_6") (pintype "input"))
      (node (ref "RN1") (pin "2") (pinfunction "2_2") (pintype "passive"))
      (node (ref "S1") (pin "9") (pinfunction "9_9") (pintype "passive"))
    )
    (net (code "106") (name "Net-(LED1-PadA)") (class "Default")
      (node (ref "LED1") (pin "A") (pinfunction "A_A") (pintype "passive"))
      (node (ref "R1") (pin "1") (pinfunction "1_1") (pintype "passive"))
    )
    (net (code "107") (name "Net-(LED2-PadA)") (class "Default")
      (node (ref "LED2") (pin "A") (pinfunction "A_A") (pintype "passive"))
      (node (ref "R2") (pin "1") (pinfunction "1_1") (pintype "passive"))
    )
    (net (code "108") (name "Net-(LED3-PadA)") (class "Default")
      (node (ref "LED3") (pin "A") (pinfunction "A_A") (pintype "passive"))
      (node (ref "R3") (pin "1") (pinfunction "1_1") (pintype "passive"))
    )
    (net (code "109") (name "Net-(U$1-CH0)") (class "Default")
      (node (ref "ANALOG_BANK0") (pin "8") (pinfunction "8_8") (pintype "passive"))
      (node (ref "U$1") (pin "1") (pinfunction "CH0_1") (pintype "input"))
    )
    (net (code "110") (name "Net-(U$1-CH1)") (class "Default")
      (node (ref "ANALOG_BANK0") (pin "7") (pinfunction "7_7") (pintype "passive"))
      (node (ref "U$1") (pin "2") (pinfunction "CH1_2") (pintype "input"))
    )
    (net (code "111") (name "Net-(U$1-CH3)") (class "Default")
      (node (ref "ANALOG_BANK0") (pin "5") (pinfunction "5_5") (pintype "passive"))
      (node (ref "U$1") (pin "4") (pinfunction "CH3_4") (pintype "input"))
    )
    (net (code "112") (name "Net-(U$1-CH4)") (class "Default")
      (node (ref "ANALOG_BANK0") (pin "4") (pinfunction "4_4") (pintype "passive"))
      (node (ref "U$1") (pin "5") (pinfunction "CH4_5") (pintype "input"))
    )
    (net (code "113") (name "Net-(U$1-CH5)") (class "Default")
      (node (ref "ANALOG_BANK0") (pin "3") (pinfunction "3_3") (pintype "passive"))
      (node (ref "U$1") (pin "6") (pinfunction "CH5_6") (pintype "input"))
    )
    (net (code "114") (name "Net-(U$1-CH6)") (class "Default")
      (node (ref "ANALOG_BANK0") (pin "2") (pinfunction "2_2") (pintype "passive"))
      (node (ref "U$1") (pin "7") (pinfunction "CH6_7") (pintype "input"))
    )
    (net (code "115") (name "Net-(U$1-CH7)") (class "Default")
      (node (ref "ANALOG_BANK0") (pin "1") (pinfunction "1_1") (pintype "passive"))
      (node (ref "U$1") (pin "8") (pinfunction "CH7_8") (pintype "input"))
    )
    (net (code "116") (name "Net-(U$1-CLK)") (class "Default")
      (node (ref "U$1") (pin "13") (pinfunction "CLK_13") (pintype "input"))
      (node (ref "U$2") (pin "13") (pinfunction "CLK_13") (pintype "input"))
      (node (ref "U$3") (pin "13") (pinfunction "CLK_13") (pintype "input"))
      (node (ref "U$4") (pin "P$11") (pinfunction "HV_RXI_1_P$11") (pintype "bidirectional"))
      (node (ref "U$5") (pin "13") (pinfunction "CLK_13") (pintype "input"))
    )
    (net (code "117") (name "Net-(U$1-DIN)") (class "Default")
      (node (ref "U$1") (pin "11") (pinfunction "DIN_11") (pintype "input"))
      (node (ref "U$2") (pin "11") (pinfunction "DIN_11") (pintype "input"))
      (node (ref "U$3") (pin "11") (pinfunction "DIN_11") (pintype "input"))
      (node (ref "U$4") (pin "P$8") (pinfunction "HV_RXI_2_P$8") (pintype "bidirectional"))
      (node (ref "U$5") (pin "11") (pinfunction "DIN_11") (pintype "input"))
    )
    (net (code "118") (name "Net-(U$1-DOUT)") (class "Default")
      (node (ref "U$1") (pin "12") (pinfunction "DOUT_12") (pintype "output"))
      (node (ref "U$2") (pin "12") (pinfunction "DOUT_12") (pintype "output"))
      (node (ref "U$3") (pin "12") (pinfunction "DOUT_12") (pintype "output"))
      (node (ref "U$4") (pin "P$7") (pinfunction "HV_TXO_2_P$7") (pintype "bidirectional"))
      (node (ref "U$5") (pin "12") (pinfunction "DOUT_12") (pintype "output"))
    )
    (net (code "119") (name "Net-(U$2-CH0)") (class "Default")
      (node (ref "ANALOG_BANK1") (pin "8") (pinfunction "8_8") (pintype "passive"))
      (node (ref "U$2") (pin "1") (pinfunction "CH0_1") (pintype "input"))
    )
    (net (code "120") (name "Net-(U$2-CH1)") (class "Default")
      (node (ref "ANALOG_BANK1") (pin "7") (pinfunction "7_7") (pintype "passive"))
      (node (ref "U$2") (pin "2") (pinfunction "CH1_2") (pintype "input"))
    )
    (net (code "121") (name "Net-(U$2-CH2)") (class "Default")
      (node (ref "ANALOG_BANK1") (pin "6") (pinfunction "6_6") (pintype "passive"))
      (node (ref "U$2") (pin "3") (pinfunction "CH2_3") (pintype "input"))
    )
    (net (code "122") (name "Net-(U$2-CH3)") (class "Default")
      (node (ref "ANALOG_BANK1") (pin "5") (pinfunction "5_5") (pintype "passive"))
      (node (ref "U$2") (pin "4") (pinfunction "CH3_4") (pintype "input"))
    )
    (net (code "123") (name "Net-(U$2-CH4)") (class "Default")
      (node (ref "ANALOG_BANK1") (pin "4") (pinfunction "4_4") (pintype "passive"))
      (node (ref "U$2") (pin "5") (pinfunction "CH4_5") (pintype "input"))
    )
    (net (code "124") (name "Net-(U$2-CH5)") (class "Default")
      (node (ref "ANALOG_BANK1") (pin "3") (pinfunction "3_3") (pintype "passive"))
      (node (ref "U$2") (pin "6") (pinfunction "CH5_6") (pintype "input"))
    )
    (net (code "125") (name "Net-(U$2-CH6)") (class "Default")
      (node (ref "ANALOG_BANK1") (pin "2") (pinfunction "2_2") (pintype "passive"))
      (node (ref "U$2") (pin "7") (pinfunction "CH6_7") (pintype "input"))
    )
    (net (code "126") (name "Net-(U$2-CH7)") (class "Default")
      (node (ref "ANALOG_BANK1") (pin "1") (pinfunction "1_1") (pintype "passive"))
      (node (ref "U$2") (pin "8") (pinfunction "CH7_8") (pintype "input"))
    )
    (net (code "127") (name "Net-(U$2-VDD)") (class "Default")
      (node (ref "U$2") (pin "15") (pinfunction "VREF_15") (pintype "power_in"))
      (node (ref "U$2") (pin "16") (pinfunction "VDD_16") (pintype "power_in"))
    )
    (net (code "128") (name "Net-(U$3-CH0)") (class "Default")
      (node (ref "ANALOG_BANK2") (pin "8") (pinfunction "8_8") (pintype "passive"))
      (node (ref "U$3") (pin "1") (pinfunction "CH0_1") (pintype "input"))
    )
    (net (code "129") (name "Net-(U$3-CH1)") (class "Default")
      (node (ref "ANALOG_BANK2") (pin "7") (pinfunction "7_7") (pintype "passive"))
      (node (ref "U$3") (pin "2") (pinfunction "CH1_2") (pintype "input"))
    )
    (net (code "130") (name "Net-(U$3-CH2)") (class "Default")
      (node (ref "ANALOG_BANK2") (pin "6") (pinfunction "6_6") (pintype "passive"))
      (node (ref "U$3") (pin "3") (pinfunction "CH2_3") (pintype "input"))
    )
    (net (code "131") (name "Net-(U$3-CH3)") (class "Default")
      (node (ref "ANALOG_BANK2") (pin "5") (pinfunction "5_5") (pintype "passive"))
      (node (ref "U$3") (pin "4") (pinfunction "CH3_4") (pintype "input"))
    )
    (net (code "132") (name "Net-(U$3-CH4)") (class "Default")
      (node (ref "ANALOG_BANK2") (pin "4") (pinfunction "4_4") (pintype "passive"))
      (node (ref "U$3") (pin "5") (pinfunction "CH4_5") (pintype "input"))
    )
    (net (code "133") (name "Net-(U$3-CH5)") (class "Default")
      (node (ref "ANALOG_BANK2") (pin "3") (pinfunction "3_3") (pintype "passive"))
      (node (ref "U$3") (pin "6") (pinfunction "CH5_6") (pintype "input"))
    )
    (net (code "134") (name "Net-(U$3-CH6)") (class "Default")
      (node (ref "ANALOG_BANK2") (pin "2") (pinfunction "2_2") (pintype "passive"))
      (node (ref "U$3") (pin "7") (pinfunction "CH6_7") (pintype "input"))
    )
    (net (code "135") (name "Net-(U$3-CH7)") (class "Default")
      (node (ref "ANALOG_BANK2") (pin "1") (pinfunction "1_1") (pintype "passive"))
      (node (ref "U$3") (pin "8") (pinfunction "CH7_8") (pintype "input"))
    )
    (net (code "136") (name "Net-(U$5-CH1)") (class "Default")
      (node (ref "ANALOG_BANK3") (pin "7") (pinfunction "7_7") (pintype "passive"))
      (node (ref "U$5") (pin "2") (pinfunction "CH1_2") (pintype "input"))
    )
    (net (code "137") (name "Net-(U$5-CH2)") (class "Default")
      (node (ref "ANALOG_BANK3") (pin "6") (pinfunction "6_6") (pintype "passive"))
      (node (ref "U$5") (pin "3") (pinfunction "CH2_3") (pintype "input"))
    )
    (net (code "138") (name "Net-(U$5-CH3)") (class "Default")
      (node (ref "ANALOG_BANK3") (pin "5") (pinfunction "5_5") (pintype "passive"))
      (node (ref "U$5") (pin "4") (pinfunction "CH3_4") (pintype "input"))
    )
    (net (code "139") (name "Net-(U$5-CH4)") (class "Default")
      (node (ref "ANALOG_BANK3") (pin "4") (pinfunction "4_4") (pintype "passive"))
      (node (ref "U$5") (pin "5") (pinfunction "CH4_5") (pintype "input"))
    )
    (net (code "140") (name "Net-(U$5-CH5)") (class "Default")
      (node (ref "ANALOG_BANK3") (pin "3") (pinfunction "3_3") (pintype "passive"))
      (node (ref "U$5") (pin "6") (pinfunction "CH5_6") (pintype "input"))
    )
    (net (code "141") (name "Net-(U$5-CH6)") (class "Default")
      (node (ref "ANALOG_BANK3") (pin "2") (pinfunction "2_2") (pintype "passive"))
      (node (ref "U$5") (pin "7") (pinfunction "CH6_7") (pintype "input"))
    )
    (net (code "142") (name "Net-(U$5-CH7)") (class "Default")
      (node (ref "ANALOG_BANK3") (pin "1") (pinfunction "1_1") (pintype "passive"))
      (node (ref "U$5") (pin "8") (pinfunction "CH7_8") (pintype "input"))
    )
    (net (code "143") (name "Net-(U1-PB0)") (class "Default")
      (node (ref "R1") (pin "2") (pinfunction "2_2") (pintype "passive"))
      (node (ref "U1") (pin "14") (pinfunction "PB0_14") (pintype "bidirectional"))
    )
    (net (code "144") (name "Net-(U1-PB1)") (class "Default")
      (node (ref "R2") (pin "2") (pinfunction "2_2") (pintype "passive"))
      (node (ref "U1") (pin "15") (pinfunction "PB1_15") (pintype "bidirectional"))
    )
    (net (code "145") (name "Net-(U1-PB2)") (class "Default")
      (node (ref "R3") (pin "2") (pinfunction "2_2") (pintype "passive"))
      (node (ref "U1") (pin "16") (pinfunction "PB2_16") (pintype "bidirectional"))
    )
    (net (code "146") (name "unconnected-(ANALOG_BANK0-Pad6)") (class "Default")
      (node (ref "ANALOG_BANK0") (pin "6") (pinfunction "6_6") (pintype "passive"))
    )
    (net (code "147") (name "unconnected-(ANALOG_BANK3-Pad8)") (class "Default")
      (node (ref "ANALOG_BANK3") (pin "8") (pinfunction "8_8") (pintype "passive"))
    )
    (net (code "148") (name "unconnected-(IC1-GPB5-Pad6)") (class "Default")
      (node (ref "IC1") (pin "6") (pinfunction "GPB5_6") (pintype "bidirectional"))
    )
    (net (code "149") (name "unconnected-(IC1-GPB6-Pad7)") (class "Default")
      (node (ref "IC1") (pin "7") (pinfunction "GPB6_7") (pintype "bidirectional"))
    )
    (net (code "150") (name "unconnected-(IC1-GPB7-Pad8)") (class "Default")
      (node (ref "IC1") (pin "8") (pinfunction "GPB7_8") (pintype "bidirectional"))
    )
    (net (code "151") (name "unconnected-(IC1-INTA-Pad20)") (class "Default")
      (node (ref "IC1") (pin "20") (pinfunction "INTA_20") (pintype "output"))
    )
    (net (code "152") (name "unconnected-(IC1-INTB-Pad19)") (class "Default")
      (node (ref "IC1") (pin "19") (pinfunction "INTB_19") (pintype "output"))
    )
    (net (code "153") (name "unconnected-(IC2-INTA-Pad20)") (class "Default")
      (node (ref "IC2") (pin "20") (pinfunction "INTA_20") (pintype "output"))
    )
    (net (code "154") (name "unconnected-(IC2-INTB-Pad19)") (class "Default")
      (node (ref "IC2") (pin "19") (pinfunction "INTB_19") (pintype "output"))
    )
    (net (code "155") (name "unconnected-(IC3-INTA-Pad20)") (class "Default")
      (node (ref "IC3") (pin "20") (pinfunction "INTA_20") (pintype "output"))
    )
    (net (code "156") (name "unconnected-(IC3-INTB-Pad19)") (class "Default")
      (node (ref "IC3") (pin "19") (pinfunction "INTB_19") (pintype "output"))
    )
    (net (code "157") (name "unconnected-(IC4A-~{QH}-Pad7)") (class "Default")
      (node (ref "IC4") (pin "7") (pinfunction "~{QH}_7") (pintype "output"))
    )
    (net (code "158") (name "unconnected-(J1-NC-Pad3)") (class "Default")
      (node (ref "J1") (pin "3") (pinfunction "NC_3") (pintype "no_connect"))
    )
    (net (code "159") (name "unconnected-(SHIFT_CON-Pad2)") (class "Default")
      (node (ref "SHIFT_CON") (pin "2") (pinfunction "2_2") (pintype "passive"))
    )
    (net (code "160") (name "unconnected-(SHIFT_OUT-Pad2)") (class "Default")
      (node (ref "SHIFT_OUT") (pin "2") (pinfunction "2_2") (pintype "passive"))
    )
    (net (code "161") (name "unconnected-(U$1-CH2-Pad3)") (class "Default")
      (node (ref "U$1") (pin "3") (pinfunction "CH2_3") (pintype "input"))
    )
    (net (code "162") (name "unconnected-(U$4-HV_TXO_1-PadP$12)") (class "Default")
      (node (ref "U$4") (pin "P$12") (pinfunction "HV_TXO_1_P$12") (pintype "bidirectional"))
    )
    (net (code "163") (name "unconnected-(U$4-LV_RXO_1-PadP$2)") (class "Default")
      (node (ref "U$4") (pin "P$2") (pinfunction "LV_RXO_1_P$2") (pintype "bidirectional"))
    )
    (net (code "164") (name "unconnected-(U$5-CH0-Pad1)") (class "Default")
      (node (ref "U$5") (pin "1") (pinfunction "CH0_1") (pintype "input"))
    )
    (net (code "165") (name "unconnected-(U1-AREF-Pad21)") (class "Default")
      (node (ref "U1") (pin "21") (pinfunction "AREF_21") (pintype "input"))
    )
    (net (code "166") (name "unconnected-(U1-PD7-Pad13)") (class "Default")
      (node (ref "U1") (pin "13") (pinfunction "PD7_13") (pintype "bidirectional"))
    )
  )
)
